# square.net
KiCad netlist of a schematic drawn in EAGLE
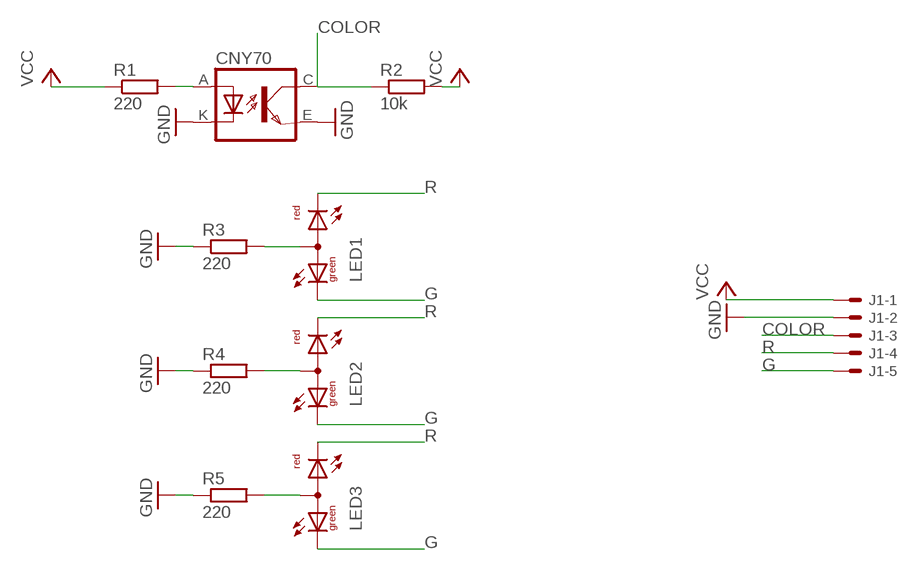
[diagram p0: schematic, sheet 1]

(export (version "E")
  (design (tool "Eeschema 10.0.6"))
  (components
    (comp (ref "CNY70")
      (value "CNY70")
      (footprint "eagle-import:4")
      (libsource (lib "eagle-import") (part "CNY70"))
    )
    (comp (ref "J1")
      (value "CON_5P_1.27")
      (footprint "eagle-import:CON_5P_1.27")
      (libsource (lib "eagle-import") (part "CON_5P_1.27"))
    )
    (comp (ref "LED1")
      (value "L-115WEGW-CA")
      (footprint "eagle-import:DUOLED-A-3MM")
      (libsource (lib "eagle-import") (part "L-115WEGW-CA"))
    )
    (comp (ref "LED2")
      (value "L-115WEGW-CA")
      (footprint "eagle-import:DUOLED-A-3MM")
      (libsource (lib "eagle-import") (part "L-115WEGW-CA"))
    )
    (comp (ref "LED3")
      (value "L-115WEGW-CA")
      (footprint "eagle-import:DUOLED-A-3MM")
      (libsource (lib "eagle-import") (part "L-115WEGW-CA"))
    )
    (comp (ref "R1")
      (value "220")
      (footprint "eagle-import:0204_7")
      (libsource (lib "eagle-import") (part "R-EU_0204/7"))
    )
    (comp (ref "R2")
      (value "10k")
      (footprint "eagle-import:0204_7")
      (libsource (lib "eagle-import") (part "R-EU_0204/7"))
    )
    (comp (ref "R3")
      (value "220")
      (footprint "eagle-import:0204_7")
      (libsource (lib "eagle-import") (part "R-EU_0204/7"))
    )
    (comp (ref "R4")
      (value "220")
      (footprint "eagle-import:0204_7")
      (libsource (lib "eagle-import") (part "R-EU_0204/7"))
    )
    (comp (ref "R5")
      (value "220")
      (footprint "eagle-import:0204_7")
      (libsource (lib "eagle-import") (part "R-EU_0204/7"))
    )
  )
  (nets
    (net (code "1") (name "/COLOR") (class "Default")
      (node (ref "CNY70") (pin "C") (pinfunction "COL_C") (pintype "passive"))
      (node (ref "J1") (pin "3") (pinfunction "S_3") (pintype "passive"))
      (node (ref "R2") (pin "1") (pinfunction "1_1") (pintype "passive"))
    )
    (net (code "2") (name "/G") (class "Default")
      (node (ref "J1") (pin "5") (pinfunction "S_5") (pintype "passive"))
      (node (ref "LED1") (pin "1") (pinfunction "CG_1") (pintype "passive"))
      (node (ref "LED2") (pin "1") (pinfunction "CG_1") (pintype "passive"))
      (node (ref "LED3") (pin "1") (pinfunction "CG_1") (pintype "passive"))
    )
    (net (code "3") (name "/R") (class "Default")
      (node (ref "J1") (pin "4") (pinfunction "S_4") (pintype "passive"))
      (node (ref "LED1") (pin "3") (pinfunction "CR_3") (pintype "passive"))
      (node (ref "LED2") (pin "3") (pinfunction "CR_3") (pintype "passive"))
      (node (ref "LED3") (pin "3") (pinfunction "CR_3") (pintype "passive"))
    )
    (net (code "4") (name "GND") (class "Default")
      (node (ref "CNY70") (pin "E") (pinfunction "EMI_E") (pintype "passive"))
      (node (ref "CNY70") (pin "K") (pinfunction "C_K") (pintype "passive"))
      (node (ref "J1") (pin "2") (pinfunction "S_2") (pintype "passive"))
      (node (ref "R3") (pin "1") (pinfunction "1_1") (pintype "passive"))
      (node (ref "R4") (pin "1") (pinfunction "1_1") (pintype "passive"))
      (node (ref "R5") (pin "1") (pinfunction "1_1") (pintype "passive"))
    )
    (net (code "5") (name "Net-(CNY70-PadA)") (class "Default")
      (node (ref "CNY70") (pin "A") (pinfunction "A_A") (pintype "passive"))
      (node (ref "R1") (pin "2") (pinfunction "2_2") (pintype "passive"))
    )
    (net (code "6") (name "Net-(LED1-A)") (class "Default")
      (node (ref "LED1") (pin "2") (pinfunction "A_2") (pintype "passive"))
      (node (ref "R3") (pin "2") (pinfunction "2_2") (pintype "passive"))
    )
    (net (code "7") (name "Net-(LED2-A)") (class "Default")
      (node (ref "LED2") (pin "2") (pinfunction "A_2") (pintype "passive"))
      (node (ref "R4") (pin "2") (pinfunction "2_2") (pintype "passive"))
    )
    (net (code "8") (name "Net-(LED3-A)") (class "Default")
      (node (ref "LED3") (pin "2") (pinfunction "A_2") (pintype "passive"))
      (node (ref "R5") (pin "2") (pinfunction "2_2") (pintype "passive"))
    )
    (net (code "9") (name "VCC") (class "Default")
      (node (ref "J1") (pin "1") (pinfunction "S_1") (pintype "passive"))
      (node (ref "R1") (pin "1") (pinfunction "1_1") (pintype "passive"))
      (node (ref "R2") (pin "2") (pinfunction "2_2") (pintype "passive"))
    )
  )
)
